# Atmega8.net
KiCad netlist of a schematic drawn in Altium Designer
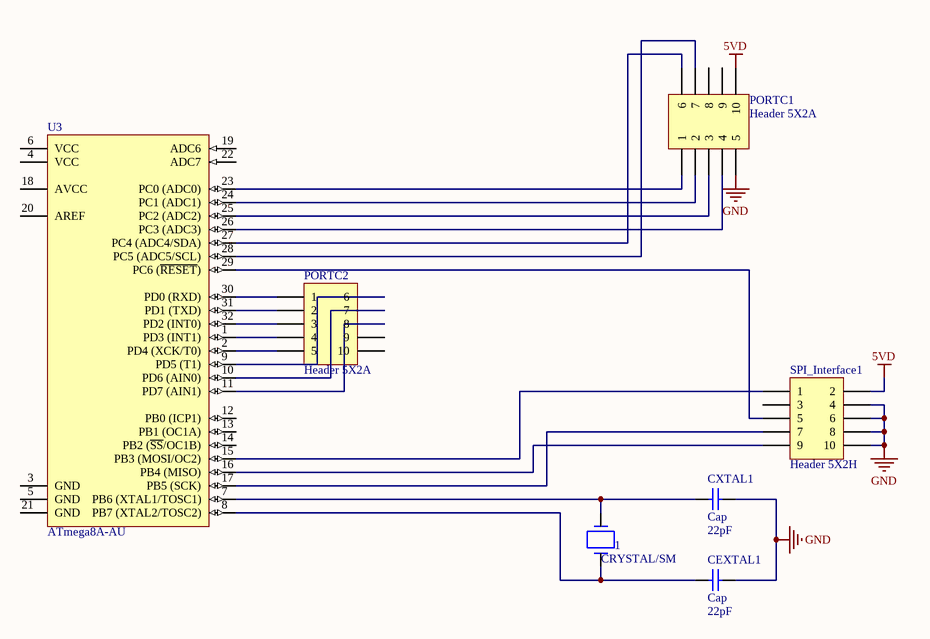
[diagram p0: Atmega8.SchDoc]

(export (version "E")
  (design (tool "Eeschema 10.0.6"))
  (components
    (comp (ref "1") (value "CRYSTAL/SM") (libsource (lib "esd_library") (part "CRYSTAL/SM")))
    (comp (ref "CEXTAL1")
      (value "Cap")
      (footprint "CAPC2012X09M")
      (description "CAP CER 22pF 630v X7R 0805")
      (fields (field (name "ALTIUM_VALUE") "22pF") (field (name "MPN") "C0805C220KBRACTU"))
      (libsource (lib "esd_library") (part "CAP-X7R-22pF-630V-±10%"))
    )
    (comp (ref "CXTAL1")
      (value "Cap")
      (footprint "CAPC2012X09M")
      (description "CAP CER 22pF 630v X7R 0805")
      (fields (field (name "ALTIUM_VALUE") "22pF") (field (name "MPN") "C0805C220KBRACTU"))
      (libsource (lib "esd_library") (part "CAP-X7R-22pF-630V-±10%"))
    )
    (comp (ref "PORTC1")
      (value "Header 5X2A")
      (footprint "HDR2X5_CEN")
      (description "Header, 5-Pin, Dual row")
      (fields (field (name "PUBLISHER") "Altium Limited"))
      (libsource (lib "Miscellaneous Connectors") (part "Header 5X2A"))
    )
    (comp (ref "PORTC2")
      (value "Header 5X2A")
      (footprint "HDR2X5_CEN")
      (description "Header, 5-Pin, Dual row")
      (fields (field (name "PUBLISHER") "Altium Limited"))
      (libsource (lib "") (part "Header 5X2A_1"))
    )
    (comp (ref "SPI_Interface1")
      (value "Header 5X2H")
      (footprint "HDR2X5H")
      (description "Header, 5-Pin, Dual row, Right Angle")
      (fields (field (name "PUBLISHER") "Altium Limited"))
      (libsource (lib "Miscellaneous Connectors") (part "Header 5X2H"))
    )
    (comp (ref "U3")
      (value "ATmega8A-AU")
      (footprint "32A_N")
      (fields (field (name "PUBLISHER") "Altium Limited"))
      (libsource (lib "Atmel Microcontroller 8-Bit megaAVR") (part "ATmega8A-AU"))
    )
  )
  (nets
    (net (code "1") (name "5VD") (class "Default")
      (node (ref "PORTC1") (pin "10") (pinfunction "10_10") (pintype "passive"))
      (node (ref "SPI_Interface1") (pin "2") (pinfunction "2_2") (pintype "passive"))
    )
    (net (code "2") (name "GND") (class "Default")
      (node (ref "CEXTAL1") (pin "1") (pinfunction "1_1") (pintype "passive"))
      (node (ref "CXTAL1") (pin "1") (pinfunction "1_1") (pintype "passive"))
      (node (ref "PORTC1") (pin "5") (pinfunction "5_5") (pintype "passive"))
      (node (ref "SPI_Interface1") (pin "10") (pinfunction "10_10") (pintype "passive"))
      (node (ref "SPI_Interface1") (pin "4") (pinfunction "4_4") (pintype "passive"))
      (node (ref "SPI_Interface1") (pin "6") (pinfunction "6_6") (pintype "passive"))
      (node (ref "SPI_Interface1") (pin "8") (pinfunction "8_8") (pintype "passive"))
    )
    (net (code "3") (name "Net-(U3-PB3_(MOSI{slash}OC2))") (class "Default")
      (node (ref "SPI_Interface1") (pin "1") (pinfunction "1_1") (pintype "passive"))
      (node (ref "U3") (pin "15") (pinfunction "PB3_(MOSI/OC2)_15") (pintype "bidirectional"))
    )
    (net (code "4") (name "Net-(U3-PB4_(MISO))") (class "Default")
      (node (ref "SPI_Interface1") (pin "9") (pinfunction "9_9") (pintype "passive"))
      (node (ref "U3") (pin "16") (pinfunction "PB4_(MISO)_16") (pintype "bidirectional"))
    )
    (net (code "5") (name "Net-(U3-PB5_(SCK))") (class "Default")
      (node (ref "SPI_Interface1") (pin "7") (pinfunction "7_7") (pintype "passive"))
      (node (ref "U3") (pin "17") (pinfunction "PB5_(SCK)_17") (pintype "bidirectional"))
    )
    (net (code "6") (name "Net-(U3-PB6_(XTAL1{slash}TOSC1))") (class "Default")
      (node (ref "1") (pin "1") (pinfunction "1_1") (pintype "passive"))
      (node (ref "CXTAL1") (pin "2") (pinfunction "2_2") (pintype "passive"))
      (node (ref "U3") (pin "7") (pinfunction "PB6_(XTAL1/TOSC1)_7") (pintype "bidirectional"))
    )
    (net (code "7") (name "Net-(U3-PB7_(XTAL2{slash}TOSC2))") (class "Default")
      (node (ref "1") (pin "2") (pinfunction "2_2") (pintype "passive"))
      (node (ref "CEXTAL1") (pin "2") (pinfunction "2_2") (pintype "passive"))
      (node (ref "U3") (pin "8") (pinfunction "PB7_(XTAL2/TOSC2)_8") (pintype "bidirectional"))
    )
    (net (code "8") (name "Net-(U3-PC0_(ADC0))") (class "Default")
      (node (ref "PORTC1") (pin "1") (pinfunction "1_1") (pintype "passive"))
      (node (ref "U3") (pin "23") (pinfunction "PC0_(ADC0)_23") (pintype "bidirectional"))
    )
    (net (code "9") (name "Net-(U3-PC1_(ADC1))") (class "Default")
      (node (ref "PORTC1") (pin "2") (pinfunction "2_2") (pintype "passive"))
      (node (ref "U3") (pin "24") (pinfunction "PC1_(ADC1)_24") (pintype "bidirectional"))
    )
    (net (code "10") (name "Net-(U3-PC2_(ADC2))") (class "Default")
      (node (ref "PORTC1") (pin "3") (pinfunction "3_3") (pintype "passive"))
      (node (ref "U3") (pin "25") (pinfunction "PC2_(ADC2)_25") (pintype "bidirectional"))
    )
    (net (code "11") (name "Net-(U3-PC3_(ADC3))") (class "Default")
      (node (ref "PORTC1") (pin "4") (pinfunction "4_4") (pintype "passive"))
      (node (ref "U3") (pin "26") (pinfunction "PC3_(ADC3)_26") (pintype "bidirectional"))
    )
    (net (code "12") (name "Net-(U3-PC4_(ADC4{slash}SDA))") (class "Default")
      (node (ref "PORTC1") (pin "6") (pinfunction "6_6") (pintype "passive"))
      (node (ref "U3") (pin "27") (pinfunction "PC4_(ADC4/SDA)_27") (pintype "bidirectional"))
    )
    (net (code "13") (name "Net-(U3-PC5_(ADC5{slash}SCL))") (class "Default")
      (node (ref "PORTC1") (pin "7") (pinfunction "7_7") (pintype "passive"))
      (node (ref "U3") (pin "28") (pinfunction "PC5_(ADC5/SCL)_28") (pintype "bidirectional"))
    )
    (net (code "14") (name "Net-(U3-PC6_(~{RESET}))") (class "Default")
      (node (ref "SPI_Interface1") (pin "5") (pinfunction "5_5") (pintype "passive"))
      (node (ref "U3") (pin "29") (pinfunction "PC6_(~{RESET})_29") (pintype "bidirectional"))
    )
    (net (code "15") (name "Net-(U3-PD0_(RXD))") (class "Default")
      (node (ref "PORTC2") (pin "1") (pinfunction "1_1") (pintype "passive"))
      (node (ref "U3") (pin "30") (pinfunction "PD0_(RXD)_30") (pintype "bidirectional"))
    )
    (net (code "16") (name "Net-(U3-PD1_(TXD))") (class "Default")
      (node (ref "PORTC2") (pin "2") (pinfunction "2_2") (pintype "passive"))
      (node (ref "U3") (pin "31") (pinfunction "PD1_(TXD)_31") (pintype "bidirectional"))
    )
    (net (code "17") (name "Net-(U3-PD2_(INT0))") (class "Default")
      (node (ref "PORTC2") (pin "3") (pinfunction "3_3") (pintype "passive"))
      (node (ref "U3") (pin "32") (pinfunction "PD2_(INT0)_32") (pintype "bidirectional"))
    )
    (net (code "18") (name "Net-(U3-PD3_(INT1))") (class "Default")
      (node (ref "PORTC2") (pin "4") (pinfunction "4_4") (pintype "passive"))
      (node (ref "U3") (pin "1") (pinfunction "PD3_(INT1)_1") (pintype "bidirectional"))
    )
    (net (code "19") (name "Net-(U3-PD4_(XCK{slash}T0))") (class "Default")
      (node (ref "PORTC2") (pin "5") (pinfunction "5_5") (pintype "passive"))
      (node (ref "U3") (pin "2") (pinfunction "PD4_(XCK/T0)_2") (pintype "bidirectional"))
    )
    (net (code "20") (name "Net-(U3-PD5_(T1))") (class "Default")
      (node (ref "PORTC2") (pin "6") (pinfunction "6_6") (pintype "passive"))
      (node (ref "U3") (pin "9") (pinfunction "PD5_(T1)_9") (pintype "bidirectional"))
    )
    (net (code "21") (name "Net-(U3-PD6_(AIN0))") (class "Default")
      (node (ref "PORTC2") (pin "7") (pinfunction "7_7") (pintype "passive"))
      (node (ref "U3") (pin "10") (pinfunction "PD6_(AIN0)_10") (pintype "bidirectional"))
    )
    (net (code "22") (name "Net-(U3-PD7_(AIN1))") (class "Default")
      (node (ref "PORTC2") (pin "8") (pinfunction "8_8") (pintype "passive"))
      (node (ref "U3") (pin "11") (pinfunction "PD7_(AIN1)_11") (pintype "bidirectional"))
    )
    (net (code "23") (name "unconnected-(PORTC1-Pad8)") (class "Default")
      (node (ref "PORTC1") (pin "8") (pinfunction "8_8") (pintype "passive"))
    )
    (net (code "24") (name "unconnected-(PORTC1-Pad9)") (class "Default")
      (node (ref "PORTC1") (pin "9") (pinfunction "9_9") (pintype "passive"))
    )
    (net (code "25") (name "unconnected-(PORTC2-Pad9)") (class "Default")
      (node (ref "PORTC2") (pin "9") (pinfunction "9_9") (pintype "passive"))
    )
    (net (code "26") (name "unconnected-(PORTC2-Pad10)") (class "Default")
      (node (ref "PORTC2") (pin "10") (pinfunction "10_10") (pintype "passive"))
    )
    (net (code "27") (name "unconnected-(SPI_Interface1-Pad3)") (class "Default")
      (node (ref "SPI_Interface1") (pin "3") (pinfunction "3_3") (pintype "passive"))
    )
    (net (code "28") (name "unconnected-(U3-ADC6-Pad19)") (class "Default")
      (node (ref "U3") (pin "19") (pinfunction "ADC6_19") (pintype "input"))
    )
    (net (code "29") (name "unconnected-(U3-ADC7-Pad22)") (class "Default")
      (node (ref "U3") (pin "22") (pinfunction "ADC7_22") (pintype "input"))
    )
    (net (code "30") (name "unconnected-(U3-AREF-Pad20)") (class "Default")
      (node (ref "U3") (pin "20") (pinfunction "AREF_20") (pintype "power_in"))
    )
    (net (code "31") (name "unconnected-(U3-AVCC-Pad18)") (class "Default")
      (node (ref "U3") (pin "18") (pinfunction "AVCC_18") (pintype "power_in"))
    )
    (net (code "32") (name "unconnected-(U3-GND-Pad3)") (class "Default")
      (node (ref "U3") (pin "3") (pinfunction "GND_3") (pintype "power_in"))
    )
    (net (code "33") (name "unconnected-(U3-GND-Pad5)") (class "Default")
      (node (ref "U3") (pin "5") (pinfunction "GND_5") (pintype "power_in"))
    )
    (net (code "34") (name "unconnected-(U3-GND-Pad21)") (class "Default")
      (node (ref "U3") (pin "21") (pinfunction "GND_21") (pintype "power_in"))
    )
    (net (code "35") (name "unconnected-(U3-PB0_(ICP1)-Pad12)") (class "Default")
      (node (ref "U3") (pin "12") (pinfunction "PB0_(ICP1)_12") (pintype "bidirectional"))
    )
    (net (code "36") (name "unconnected-(U3-PB1_(OC1A)-Pad13)") (class "Default")
      (node (ref "U3") (pin "13") (pinfunction "PB1_(OC1A)_13") (pintype "bidirectional"))
    )
    (net (code "37") (name "unconnected-(U3-PB2_(~{SS}{slash}OC1B)-Pad14)") (class "Default")
      (node (ref "U3") (pin "14") (pinfunction "PB2_(~{SS}/OC1B)_14") (pintype "bidirectional"))
    )
    (net (code "38") (name "unconnected-(U3-VCC-Pad4)") (class "Default")
      (node (ref "U3") (pin "4") (pinfunction "VCC_4") (pintype "power_in"))
    )
    (net (code "39") (name "unconnected-(U3-VCC-Pad6)") (class "Default")
      (node (ref "U3") (pin "6") (pinfunction "VCC_6") (pintype "power_in"))
    )
  )
)
